# smartGarden_COM_Rev01.net
KiCad netlist of a schematic drawn in Altium Designer
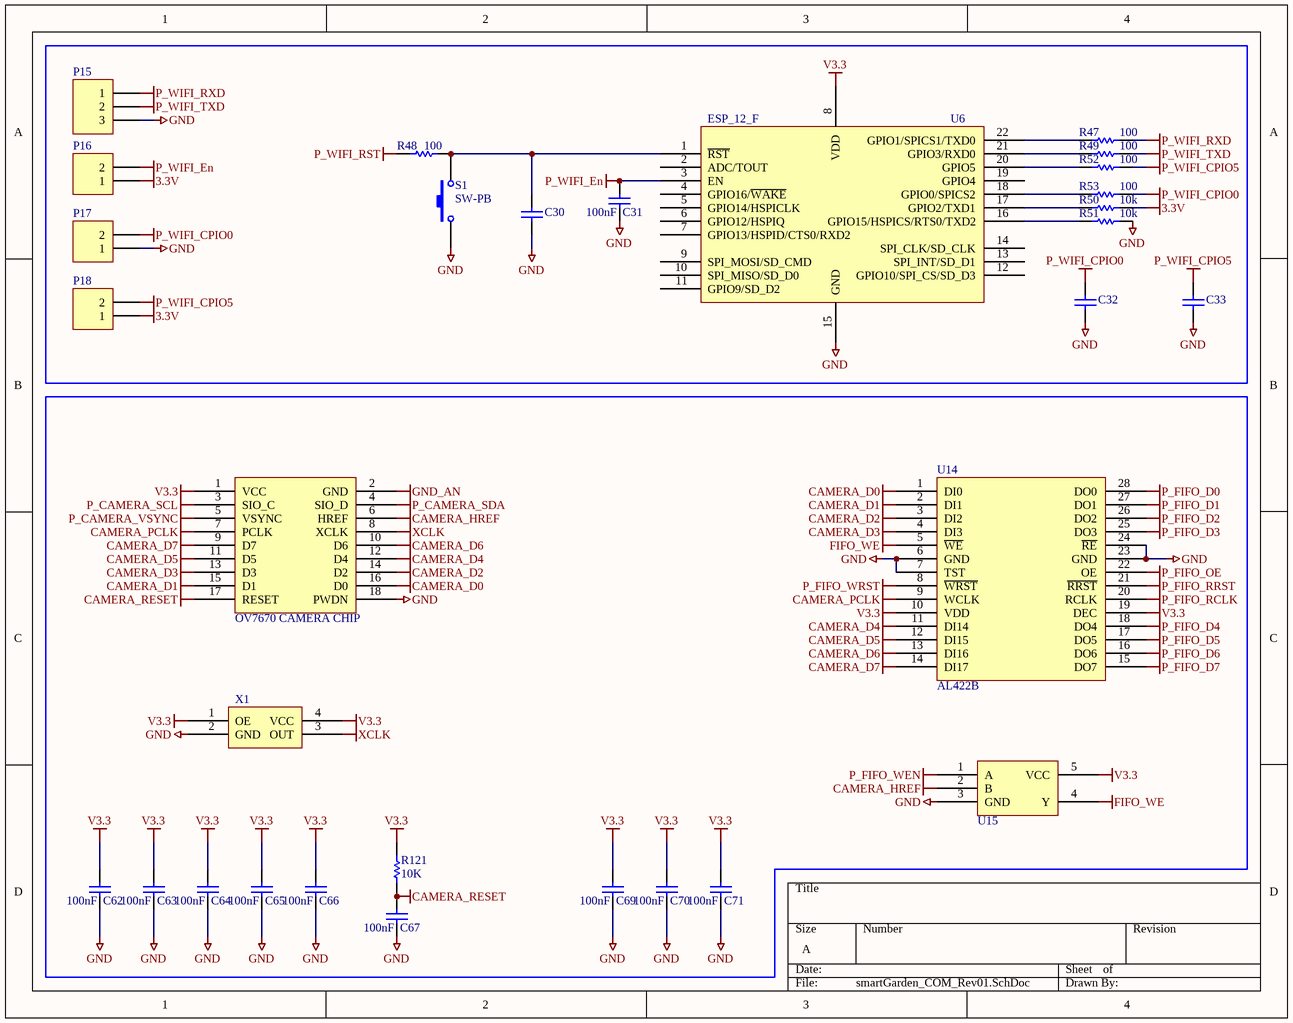
[diagram p0: smartGarden_COM_Rev01.SchDoc]

(export (version "E")
  (design (tool "Eeschema 10.0.6"))
  (components
    (comp (ref "C30")
      (value "100nF_SKIP")
      (footprint "0805_smd")
      (description "Capacitor (Semiconductor SIM Model)")
      (fields (field (name "PUBLISHER") "Altium Limited"))
      (libsource (lib "Miscellaneous Devices") (part "Cap Semi"))
    )
    (comp (ref "C31")
      (value "100nF")
      (footprint "0805_SMD")
      (description "Capacitor (Semiconductor SIM Model)")
      (fields (field (name "PUBLISHER") "Altium Limited"))
      (libsource (lib "Miscellaneous Devices") (part "Cap Semi"))
    )
    (comp (ref "C32")
      (value "100n_skip")
      (footprint "0805_SMD")
      (description "Capacitor (Semiconductor SIM Model)")
      (fields (field (name "PUBLISHER") "Altium Limited"))
      (libsource (lib "Miscellaneous Devices") (part "Cap Semi"))
    )
    (comp (ref "C33")
      (value "100n_skip")
      (footprint "0805_SMD")
      (description "Capacitor (Semiconductor SIM Model)")
      (fields (field (name "PUBLISHER") "Altium Limited"))
      (libsource (lib "Miscellaneous Devices") (part "Cap Semi"))
    )
    (comp (ref "C62")
      (value "100nF")
      (footprint "0805_SMD")
      (description "Capacitor (Semiconductor SIM Model)")
      (fields (field (name "PUBLISHER") "Altium Limited"))
      (libsource (lib "Miscellaneous Devices") (part "Cap Semi"))
    )
    (comp (ref "C63")
      (value "100nF")
      (footprint "0805_SMD")
      (description "Capacitor (Semiconductor SIM Model)")
      (fields (field (name "PUBLISHER") "Altium Limited"))
      (libsource (lib "Miscellaneous Devices") (part "Cap Semi"))
    )
    (comp (ref "C64")
      (value "100nF")
      (footprint "0805_SMD")
      (description "Capacitor (Semiconductor SIM Model)")
      (fields (field (name "PUBLISHER") "Altium Limited"))
      (libsource (lib "Miscellaneous Devices") (part "Cap Semi"))
    )
    (comp (ref "C65")
      (value "100nF")
      (footprint "0805_SMD")
      (description "Capacitor (Semiconductor SIM Model)")
      (fields (field (name "PUBLISHER") "Altium Limited"))
      (libsource (lib "Miscellaneous Devices") (part "Cap Semi"))
    )
    (comp (ref "C66")
      (value "100nF")
      (footprint "0805_SMD")
      (description "Capacitor (Semiconductor SIM Model)")
      (fields (field (name "PUBLISHER") "Altium Limited"))
      (libsource (lib "Miscellaneous Devices") (part "Cap Semi"))
    )
    (comp (ref "C67")
      (value "100nF")
      (footprint "0805_SMD")
      (description "Capacitor (Semiconductor SIM Model)")
      (fields (field (name "PUBLISHER") "Altium Limited"))
      (libsource (lib "Miscellaneous Devices") (part "Cap Semi"))
    )
    (comp (ref "C69")
      (value "100nF")
      (footprint "0805_SMD")
      (description "Capacitor (Semiconductor SIM Model)")
      (fields (field (name "PUBLISHER") "Altium Limited"))
      (libsource (lib "Miscellaneous Devices") (part "Cap Semi"))
    )
    (comp (ref "C70")
      (value "100nF")
      (footprint "0805_SMD")
      (description "Capacitor (Semiconductor SIM Model)")
      (fields (field (name "PUBLISHER") "Altium Limited"))
      (libsource (lib "Miscellaneous Devices") (part "Cap Semi"))
    )
    (comp (ref "C71")
      (value "100nF")
      (footprint "0805_SMD")
      (description "Capacitor (Semiconductor SIM Model)")
      (fields (field (name "PUBLISHER") "Altium Limited"))
      (libsource (lib "Miscellaneous Devices") (part "Cap Semi"))
    )
    (comp (ref "P15")
      (value "CON 1*40 PIN HEADER 5H MALE 2.54")
      (footprint "CON3_XH")
      (description "Header, 3-Pin")
      (fields (field (name "PUBLISHER") "Altium Limited"))
      (libsource (lib "Miscellaneous Connectors") (part "Header 3"))
    )
    (comp (ref "P16")
      (value "Header 2")
      (footprint "HDR1X2")
      (description "Header, 2-Pin")
      (fields (field (name "PUBLISHER") "Altium Limited"))
      (libsource (lib "Miscellaneous Connectors") (part "Header 2"))
    )
    (comp (ref "P17")
      (value "Header 2")
      (footprint "HDR1X2")
      (description "Header, 2-Pin")
      (fields (field (name "PUBLISHER") "Altium Limited"))
      (libsource (lib "Miscellaneous Connectors") (part "Header 2"))
    )
    (comp (ref "P18")
      (value "Header 2")
      (footprint "HDR1X2")
      (description "Header, 2-Pin")
      (fields (field (name "PUBLISHER") "Altium Limited"))
      (libsource (lib "Miscellaneous Connectors") (part "Header 2"))
    )
    (comp (ref "R47")
      (value "100")
      (footprint "0805_smd")
      (description "Semiconductor Resistor")
      (fields (field (name "PUBLISHER") "Altium Limited"))
      (libsource (lib "Miscellaneous Devices") (part "Res Semi"))
    )
    (comp (ref "R48")
      (value "100")
      (footprint "0805_smd")
      (description "Semiconductor Resistor")
      (fields (field (name "PUBLISHER") "Altium Limited"))
      (libsource (lib "Miscellaneous Devices") (part "Res Semi"))
    )
    (comp (ref "R49")
      (value "100")
      (footprint "0805_smd")
      (description "Semiconductor Resistor")
      (fields (field (name "PUBLISHER") "Altium Limited"))
      (libsource (lib "Miscellaneous Devices") (part "Res Semi"))
    )
    (comp (ref "R50")
      (value "10k")
      (footprint "0805_smd")
      (description "Semiconductor Resistor")
      (fields (field (name "PUBLISHER") "Altium Limited"))
      (libsource (lib "Miscellaneous Devices") (part "Res Semi"))
    )
    (comp (ref "R51")
      (value "10k")
      (footprint "0805_smd")
      (description "Semiconductor Resistor")
      (fields (field (name "PUBLISHER") "Altium Limited"))
      (libsource (lib "Miscellaneous Devices") (part "Res Semi"))
    )
    (comp (ref "R52")
      (value "100")
      (footprint "0805_smd")
      (description "Semiconductor Resistor")
      (fields (field (name "PUBLISHER") "Altium Limited"))
      (libsource (lib "Miscellaneous Devices") (part "Res Semi"))
    )
    (comp (ref "R53")
      (value "100")
      (footprint "0805_smd")
      (description "Semiconductor Resistor")
      (fields (field (name "PUBLISHER") "Altium Limited"))
      (libsource (lib "Miscellaneous Devices") (part "Res Semi"))
    )
    (comp (ref "R121")
      (value "10K")
      (footprint "0805_smd")
      (description "Semiconductor Resistor")
      (fields (field (name "PUBLISHER") "Altium Limited"))
      (libsource (lib "Miscellaneous Devices") (part "Res Semi"))
    )
    (comp (ref "S1")
      (value "SW-PB")
      (footprint "SW_4.5*4.5")
      (description "Switch")
      (fields (field (name "PUBLISHER") "Altium Limited"))
      (libsource (lib "Miscellaneous Devices") (part "SW-PB"))
    )
    (comp (ref "U6")
      (value "ESP_12_F")
      (footprint "ESP_12_E")
      (description "ESP-12 Wi-Fi Module by AI-Thinker")
      (libsource (lib "ESP-12") (part "ESP_12_E"))
    )
    (comp (ref "U13") (value "OV7670 CAMERA CHIP") (libsource (lib "MYLib524") (part "OV7670 CAMERA CHIP")))
    (comp (ref "U14") (value "AL422B") (libsource (lib "MYLib524") (part "AL422B")))
    (comp (ref "U15") (value "NAND") (libsource (lib "MYLib524") (part "SN74LVC1G00")))
    (comp (ref "X1") (value "4PIN OSCILLATOR") (libsource (lib "MYLib524") (part "4PIN OSCILLATOR")))
  )
  (nets
    (net (code "1") (name "3.3V") (class "Default")
      (node (ref "P16") (pin "1") (pinfunction "1_1") (pintype "passive"))
      (node (ref "P18") (pin "1") (pinfunction "1_1") (pintype "passive"))
      (node (ref "R50") (pin "1") (pinfunction "1_1") (pintype "passive"))
    )
    (net (code "2") (name "CAMERA_D0") (class "Default")
      (node (ref "U13") (pin "16") (pinfunction "D0_16") (pintype "passive"))
      (node (ref "U14") (pin "1") (pinfunction "DI0_1") (pintype "passive"))
    )
    (net (code "3") (name "CAMERA_D1") (class "Default")
      (node (ref "U13") (pin "15") (pinfunction "D1_15") (pintype "passive"))
      (node (ref "U14") (pin "2") (pinfunction "DI1_2") (pintype "passive"))
    )
    (net (code "4") (name "CAMERA_D2") (class "Default")
      (node (ref "U13") (pin "14") (pinfunction "D2_14") (pintype "passive"))
      (node (ref "U14") (pin "3") (pinfunction "DI2_3") (pintype "passive"))
    )
    (net (code "5") (name "CAMERA_D3") (class "Default")
      (node (ref "U13") (pin "13") (pinfunction "D3_13") (pintype "passive"))
      (node (ref "U14") (pin "4") (pinfunction "DI3_4") (pintype "passive"))
    )
    (net (code "6") (name "CAMERA_D4") (class "Default")
      (node (ref "U13") (pin "12") (pinfunction "D4_12") (pintype "passive"))
      (node (ref "U14") (pin "11") (pinfunction "DI14_11") (pintype "passive"))
    )
    (net (code "7") (name "CAMERA_D5") (class "Default")
      (node (ref "U13") (pin "11") (pinfunction "D5_11") (pintype "passive"))
      (node (ref "U14") (pin "12") (pinfunction "DI15_12") (pintype "passive"))
    )
    (net (code "8") (name "CAMERA_D6") (class "Default")
      (node (ref "U13") (pin "10") (pinfunction "D6_10") (pintype "passive"))
      (node (ref "U14") (pin "13") (pinfunction "DI16_13") (pintype "passive"))
    )
    (net (code "9") (name "CAMERA_D7") (class "Default")
      (node (ref "U13") (pin "9") (pinfunction "D7_9") (pintype "passive"))
      (node (ref "U14") (pin "14") (pinfunction "DI17_14") (pintype "passive"))
    )
    (net (code "10") (name "CAMERA_HREF") (class "Default")
      (node (ref "U13") (pin "6") (pinfunction "HREF_6") (pintype "passive"))
      (node (ref "U15") (pin "2") (pinfunction "B_2") (pintype "passive"))
    )
    (net (code "11") (name "CAMERA_PCLK") (class "Default")
      (node (ref "U13") (pin "7") (pinfunction "PCLK_7") (pintype "passive"))
      (node (ref "U14") (pin "9") (pinfunction "WCLK_9") (pintype "passive"))
    )
    (net (code "12") (name "CAMERA_RESET") (class "Default")
      (node (ref "C67") (pin "2") (pinfunction "2_2") (pintype "passive"))
      (node (ref "R121") (pin "2") (pinfunction "2_2") (pintype "passive"))
      (node (ref "U13") (pin "17") (pinfunction "RESET_17") (pintype "passive"))
    )
    (net (code "13") (name "FIFO_WE") (class "Default")
      (node (ref "U14") (pin "5") (pinfunction "~{WE}_5") (pintype "passive"))
      (node (ref "U15") (pin "4") (pinfunction "Y_4") (pintype "passive"))
    )
    (net (code "14") (name "GND") (class "Default")
      (node (ref "C30") (pin "1") (pinfunction "1_1") (pintype "passive"))
      (node (ref "C31") (pin "1") (pinfunction "1_1") (pintype "passive"))
      (node (ref "C32") (pin "1") (pinfunction "1_1") (pintype "passive"))
      (node (ref "C33") (pin "1") (pinfunction "1_1") (pintype "passive"))
      (node (ref "C62") (pin "1") (pinfunction "1_1") (pintype "passive"))
      (node (ref "C63") (pin "1") (pinfunction "1_1") (pintype "passive"))
      (node (ref "C64") (pin "1") (pinfunction "1_1") (pintype "passive"))
      (node (ref "C65") (pin "1") (pinfunction "1_1") (pintype "passive"))
      (node (ref "C66") (pin "1") (pinfunction "1_1") (pintype "passive"))
      (node (ref "C67") (pin "1") (pinfunction "1_1") (pintype "passive"))
      (node (ref "C69") (pin "1") (pinfunction "1_1") (pintype "passive"))
      (node (ref "C70") (pin "1") (pinfunction "1_1") (pintype "passive"))
      (node (ref "C71") (pin "1") (pinfunction "1_1") (pintype "passive"))
      (node (ref "P15") (pin "3") (pinfunction "3_3") (pintype "passive"))
      (node (ref "P17") (pin "1") (pinfunction "1_1") (pintype "passive"))
      (node (ref "R51") (pin "1") (pinfunction "1_1") (pintype "passive"))
      (node (ref "S1") (pin "1") (pinfunction "1_1") (pintype "passive"))
      (node (ref "U13") (pin "18") (pinfunction "PWDN_18") (pintype "passive"))
      (node (ref "U14") (pin "23") (pinfunction "GND_23") (pintype "passive"))
      (node (ref "U14") (pin "24") (pinfunction "~{RE}_24") (pintype "passive"))
      (node (ref "U14") (pin "6") (pinfunction "GND_6") (pintype "passive"))
      (node (ref "U14") (pin "7") (pinfunction "TST_7") (pintype "passive"))
      (node (ref "U15") (pin "3") (pinfunction "GND_3") (pintype "passive"))
      (node (ref "U6") (pin "15") (pinfunction "GND_15") (pintype "passive"))
      (node (ref "X1") (pin "2") (pinfunction "GND_2") (pintype "passive"))
    )
    (net (code "15") (name "GND_AN") (class "Default")
      (node (ref "U13") (pin "2") (pinfunction "GND_2") (pintype "passive"))
    )
    (net (code "16") (name "Net-(U6-GPIO0{slash}SPICS2)") (class "Default")
      (node (ref "R53") (pin "2") (pinfunction "2_2") (pintype "passive"))
      (node (ref "U6") (pin "18") (pinfunction "GPIO0/SPICS2_18") (pintype "passive"))
    )
    (net (code "17") (name "Net-(U6-GPIO1{slash}SPICS1{slash}TXD0)") (class "Default")
      (node (ref "R47") (pin "2") (pinfunction "2_2") (pintype "passive"))
      (node (ref "U6") (pin "22") (pinfunction "GPIO1/SPICS1/TXD0_22") (pintype "passive"))
    )
    (net (code "18") (name "Net-(U6-GPIO2{slash}TXD1)") (class "Default")
      (node (ref "R50") (pin "2") (pinfunction "2_2") (pintype "passive"))
      (node (ref "U6") (pin "17") (pinfunction "GPIO2/TXD1_17") (pintype "passive"))
    )
    (net (code "19") (name "Net-(U6-GPIO3{slash}RXD0)") (class "Default")
      (node (ref "R49") (pin "2") (pinfunction "2_2") (pintype "passive"))
      (node (ref "U6") (pin "21") (pinfunction "GPIO3/RXD0_21") (pintype "passive"))
    )
    (net (code "20") (name "Net-(U6-GPIO5)") (class "Default")
      (node (ref "R52") (pin "2") (pinfunction "2_2") (pintype "passive"))
      (node (ref "U6") (pin "20") (pinfunction "GPIO5_20") (pintype "passive"))
    )
    (net (code "21") (name "Net-(U6-GPIO15{slash}HSPICS{slash}RTS0{slash}TXD2)") (class "Default")
      (node (ref "R51") (pin "2") (pinfunction "2_2") (pintype "passive"))
      (node (ref "U6") (pin "16") (pinfunction "GPIO15/HSPICS/RTS0/TXD2_16") (pintype "passive"))
    )
    (net (code "22") (name "Net-(U6-~{RST})") (class "Default")
      (node (ref "C30") (pin "2") (pinfunction "2_2") (pintype "passive"))
      (node (ref "R48") (pin "1") (pinfunction "1_1") (pintype "passive"))
      (node (ref "S1") (pin "2") (pinfunction "2_2") (pintype "passive"))
      (node (ref "U6") (pin "1") (pinfunction "~{RST}_1") (pintype "passive"))
    )
    (net (code "23") (name "P_CAMERA_SCL") (class "Default")
      (node (ref "U13") (pin "3") (pinfunction "SIO_C_3") (pintype "passive"))
    )
    (net (code "24") (name "P_CAMERA_SDA") (class "Default")
      (node (ref "U13") (pin "4") (pinfunction "SIO_D_4") (pintype "passive"))
    )
    (net (code "25") (name "P_CAMERA_VSYNC") (class "Default")
      (node (ref "U13") (pin "5") (pinfunction "VSYNC_5") (pintype "passive"))
    )
    (net (code "26") (name "P_FIFO_D0") (class "Default")
      (node (ref "U14") (pin "28") (pinfunction "DO0_28") (pintype "passive"))
    )
    (net (code "27") (name "P_FIFO_D1") (class "Default")
      (node (ref "U14") (pin "27") (pinfunction "DO1_27") (pintype "passive"))
    )
    (net (code "28") (name "P_FIFO_D2") (class "Default")
      (node (ref "U14") (pin "26") (pinfunction "DO2_26") (pintype "passive"))
    )
    (net (code "29") (name "P_FIFO_D3") (class "Default")
      (node (ref "U14") (pin "25") (pinfunction "DO3_25") (pintype "passive"))
    )
    (net (code "30") (name "P_FIFO_D4") (class "Default")
      (node (ref "U14") (pin "18") (pinfunction "DO4_18") (pintype "passive"))
    )
    (net (code "31") (name "P_FIFO_D5") (class "Default")
      (node (ref "U14") (pin "17") (pinfunction "DO5_17") (pintype "passive"))
    )
    (net (code "32") (name "P_FIFO_D6") (class "Default")
      (node (ref "U14") (pin "16") (pinfunction "DO6_16") (pintype "passive"))
    )
    (net (code "33") (name "P_FIFO_D7") (class "Default")
      (node (ref "U14") (pin "15") (pinfunction "DO7_15") (pintype "passive"))
    )
    (net (code "34") (name "P_FIFO_OE") (class "Default")
      (node (ref "U14") (pin "22") (pinfunction "OE_22") (pintype "passive"))
    )
    (net (code "35") (name "P_FIFO_RCLK") (class "Default")
      (node (ref "U14") (pin "20") (pinfunction "RCLK_20") (pintype "passive"))
    )
    (net (code "36") (name "P_FIFO_RRST") (class "Default")
      (node (ref "U14") (pin "21") (pinfunction "~{RRST}_21") (pintype "passive"))
    )
    (net (code "37") (name "P_FIFO_WEN") (class "Default")
      (node (ref "U15") (pin "1") (pinfunction "A_1") (pintype "passive"))
    )
    (net (code "38") (name "P_FIFO_WRST") (class "Default")
      (node (ref "U14") (pin "8") (pinfunction "~{WRST}_8") (pintype "passive"))
    )
    (net (code "39") (name "P_WIFI_CPIO0") (class "Default")
      (node (ref "C32") (pin "2") (pinfunction "2_2") (pintype "passive"))
      (node (ref "P17") (pin "2") (pinfunction "2_2") (pintype "passive"))
      (node (ref "R53") (pin "1") (pinfunction "1_1") (pintype "passive"))
    )
    (net (code "40") (name "P_WIFI_CPIO5") (class "Default")
      (node (ref "C33") (pin "2") (pinfunction "2_2") (pintype "passive"))
      (node (ref "P18") (pin "2") (pinfunction "2_2") (pintype "passive"))
      (node (ref "R52") (pin "1") (pinfunction "1_1") (pintype "passive"))
    )
    (net (code "41") (name "P_WIFI_En") (class "Default")
      (node (ref "C31") (pin "2") (pinfunction "2_2") (pintype "passive"))
      (node (ref "P16") (pin "2") (pinfunction "2_2") (pintype "passive"))
      (node (ref "U6") (pin "3") (pinfunction "EN_3") (pintype "passive"))
    )
    (net (code "42") (name "P_WIFI_RST") (class "Default")
      (node (ref "R48") (pin "2") (pinfunction "2_2") (pintype "passive"))
    )
    (net (code "43") (name "P_WIFI_RXD") (class "Default")
      (node (ref "P15") (pin "1") (pinfunction "1_1") (pintype "passive"))
      (node (ref "R47") (pin "1") (pinfunction "1_1") (pintype "passive"))
    )
    (net (code "44") (name "P_WIFI_TXD") (class "Default")
      (node (ref "P15") (pin "2") (pinfunction "2_2") (pintype "passive"))
      (node (ref "R49") (pin "1") (pinfunction "1_1") (pintype "passive"))
    )
    (net (code "45") (name "V3.3") (class "Default")
      (node (ref "C62") (pin "2") (pinfunction "2_2") (pintype "passive"))
      (node (ref "C63") (pin "2") (pinfunction "2_2") (pintype "passive"))
      (node (ref "C64") (pin "2") (pinfunction "2_2") (pintype "passive"))
      (node (ref "C65") (pin "2") (pinfunction "2_2") (pintype "passive"))
      (node (ref "C66") (pin "2") (pinfunction "2_2") (pintype "passive"))
      (node (ref "C69") (pin "2") (pinfunction "2_2") (pintype "passive"))
      (node (ref "C70") (pin "2") (pinfunction "2_2") (pintype "passive"))
      (node (ref "C71") (pin "2") (pinfunction "2_2") (pintype "passive"))
      (node (ref "R121") (pin "1") (pinfunction "1_1") (pintype "passive"))
      (node (ref "U13") (pin "1") (pinfunction "VCC_1") (pintype "passive"))
      (node (ref "U14") (pin "10") (pinfunction "VDD_10") (pintype "passive"))
      (node (ref "U14") (pin "19") (pinfunction "DEC_19") (pintype "passive"))
      (node (ref "U15") (pin "5") (pinfunction "VCC_5") (pintype "passive"))
      (node (ref "U6") (pin "8") (pinfunction "VDD_8") (pintype "passive"))
      (node (ref "X1") (pin "1") (pinfunction "OE_1") (pintype "passive"))
      (node (ref "X1") (pin "4") (pinfunction "VCC_4") (pintype "passive"))
    )
    (net (code "46") (name "XCLK") (class "Default")
      (node (ref "U13") (pin "8") (pinfunction "XCLK_8") (pintype "passive"))
      (node (ref "X1") (pin "3") (pinfunction "OUT_3") (pintype "passive"))
    )
    (net (code "47") (name "unconnected-(U6-ADC{slash}TOUT-Pad2)") (class "Default")
      (node (ref "U6") (pin "2") (pinfunction "ADC/TOUT_2") (pintype "passive"))
    )
    (net (code "48") (name "unconnected-(U6-GPIO4-Pad19)") (class "Default")
      (node (ref "U6") (pin "19") (pinfunction "GPIO4_19") (pintype "passive"))
    )
    (net (code "49") (name "unconnected-(U6-GPIO9{slash}SD_D2-Pad11)") (class "Default")
      (node (ref "U6") (pin "11") (pinfunction "GPIO9/SD_D2_11") (pintype "passive"))
    )
    (net (code "50") (name "unconnected-(U6-GPIO10{slash}SPI_CS{slash}SD_D3-Pad12)") (class "Default")
      (node (ref "U6") (pin "12") (pinfunction "GPIO10/SPI_CS/SD_D3_12") (pintype "passive"))
    )
    (net (code "51") (name "unconnected-(U6-GPIO12{slash}HSPIQ-Pad6)") (class "Default")
      (node (ref "U6") (pin "6") (pinfunction "GPIO12/HSPIQ_6") (pintype "passive"))
    )
    (net (code "52") (name "unconnected-(U6-GPIO13{slash}HSPID{slash}CTS0{slash}RXD2-Pad7)") (class "Default")
      (node (ref "U6") (pin "7") (pinfunction "GPIO13/HSPID/CTS0/RXD2_7") (pintype "passive"))
    )
    (net (code "53") (name "unconnected-(U6-GPIO14{slash}HSPICLK-Pad5)") (class "Default")
      (node (ref "U6") (pin "5") (pinfunction "GPIO14/HSPICLK_5") (pintype "passive"))
    )
    (net (code "54") (name "unconnected-(U6-GPIO16{slash}~{WAKE}-Pad4)") (class "Default")
      (node (ref "U6") (pin "4") (pinfunction "GPIO16/~{WAKE}_4") (pintype "passive"))
    )
    (net (code "55") (name "unconnected-(U6-SPI_CLK{slash}SD_CLK-Pad14)") (class "Default")
      (node (ref "U6") (pin "14") (pinfunction "SPI_CLK/SD_CLK_14") (pintype "passive"))
    )
    (net (code "56") (name "unconnected-(U6-SPI_INT{slash}SD_D1-Pad13)") (class "Default")
      (node (ref "U6") (pin "13") (pinfunction "SPI_INT/SD_D1_13") (pintype "passive"))
    )
    (net (code "57") (name "unconnected-(U6-SPI_MISO{slash}SD_D0-Pad10)") (class "Default")
      (node (ref "U6") (pin "10") (pinfunction "SPI_MISO/SD_D0_10") (pintype "passive"))
    )
    (net (code "58") (name "unconnected-(U6-SPI_MOSI{slash}SD_CMD-Pad9)") (class "Default")
      (node (ref "U6") (pin "9") (pinfunction "SPI_MOSI/SD_CMD_9") (pintype "passive"))
    )
  )
)
